# Voeding.net
KiCad netlist of a schematic drawn in Altium Designer
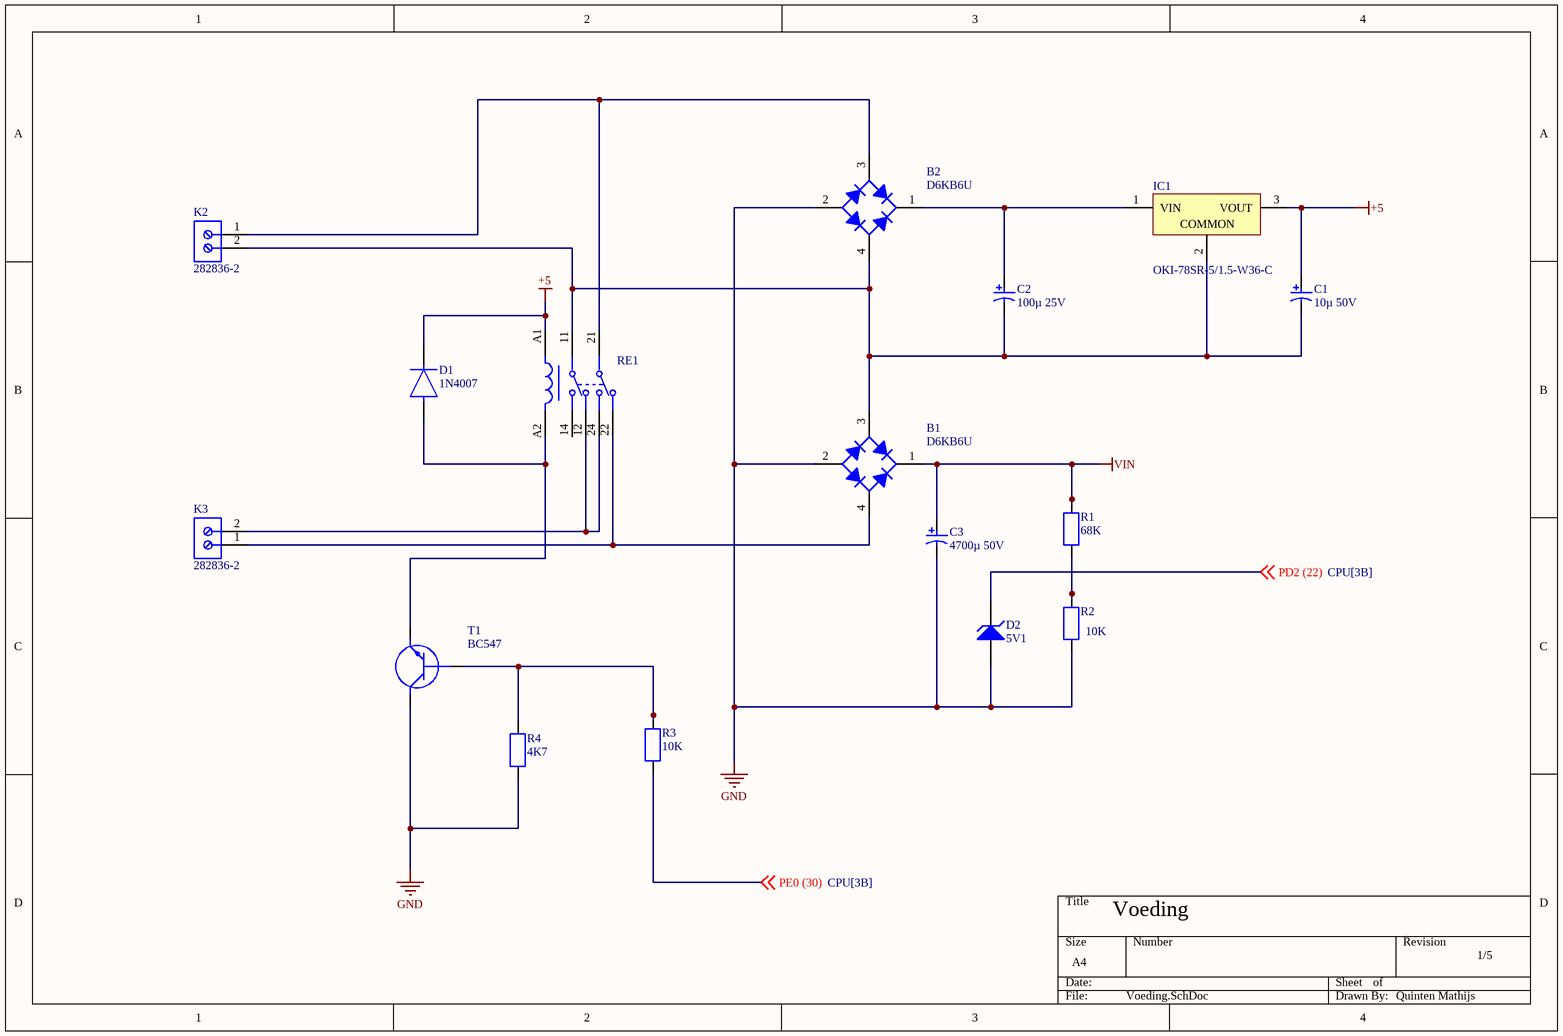
[diagram p0: Voeding.SchDoc]

(export (version "E")
  (design (tool "Eeschema 10.0.6"))
  (components
    (comp (ref "B1")
      (value "D6KB6U")
      (footprint "ttf")
      (fields (field (name "MANUFACTURER") "Diodes Inc"))
      (libsource (lib "Schem_Soldeerstation") (part "Bridge_Rectifier"))
    )
    (comp (ref "B2")
      (value "D6KB6U")
      (footprint "ttf")
      (fields (field (name "MANUFACTURER") "Diodes Inc"))
      (libsource (lib "Schem_Soldeerstation") (part "Bridge_Rectifier"))
    )
    (comp (ref "C1")
      (value "10µ 50V")
      (footprint "CE_D8_L10")
      (fields (field (name "MANUFACTURER") "Panasonic"))
      (libsource (lib "Schem_Soldeerstation") (part "Capacitor_Electrolytic"))
    )
    (comp (ref "C2")
      (value "100µ 25V")
      (footprint "CE_D8_L10")
      (fields (field (name "MANUFACTURER") "Panasonic"))
      (libsource (lib "Schem_Soldeerstation") (part "Capacitor_Electrolytic"))
    )
    (comp (ref "C3")
      (value "4700µ 50V")
      (footprint "CE_D25_L25_plugin")
      (fields (field (name "MANUFACTURER") "Panasonic"))
      (libsource (lib "Schem_Soldeerstation") (part "Capacitor_Electrolytic"))
    )
    (comp (ref "D1")
      (value "1N4007")
      (footprint "SOD-123FL")
      (fields
        (field (name "MANUFACTURER") "Diotec")
        (field (name "OCTOPART") "https://octopart.com/1n4007-diotec-4040411")
      )
      (libsource (lib "Schem_Soldeerstation") (part "Diode"))
    )
    (comp (ref "D2")
      (value "5V1")
      (footprint "SOD-123FL")
      (fields (field (name "MANUFACTURER") "On Semiconductor") (field (name "PARTNUMBER") "1SMB5920BT3G"))
      (libsource (lib "Schem_Soldeerstation") (part "Zener_Diode"))
    )
    (comp (ref "IC1")
      (value "OKI-78SR-5/1.5-W36-C")
      (footprint "OKI78SR515W36C")
      (description "Non-Isolated DC/DC Converter, 7.5 W, 7 to 36 V, 1.5 A, -40 to 85 degC, 3-Pin THD, RoHS")
      (fields (field (name "MANUFACTURER") "Murata"))
      (libsource (lib "Schem_Soldeerstation") (part "OKI-78SR-5/1.5-W36-C"))
    )
    (comp (ref "K2")
      (value "282836-2")
      (footprint "TECO-282836-2_V")
      (description "Female Header, Pitch 5 mm, 1 x 2 Position, Height 10 mm, Tail Length 3.5 mm, Rohs, Bulk")
      (fields (field (name "VOLTAGE") "300V") (field (name "MANUFACTURER") "TE Connectivity"))
      (libsource (lib "Schem_Soldeerstation") (part "CMP-1684-00017-1"))
    )
    (comp (ref "K3")
      (value "282836-2")
      (footprint "TECO-282836-2_V")
      (description "Female Header, Pitch 5 mm, 1 x 2 Position, Height 10 mm, Tail Length 3.5 mm, Rohs, Bulk")
      (fields (field (name "VOLTAGE") "300V") (field (name "MANUFACTURER") "TE Connectivity"))
      (libsource (lib "Schem_Soldeerstation") (part "CMP-1684-00017-1"))
    )
    (comp (ref "R1")
      (value "68K")
      (footprint "R_0805_L")
      (description "Resistor")
      (fields (field (name "MANUFACTURER") "Vishay Dale") (field (name "PART NUMBER") "CRCW08050000Z0EA"))
      (libsource (lib "Schem_Soldeerstation") (part "0805 (Resistor)"))
    )
    (comp (ref "R2")
      (value "10K")
      (footprint "R_0805_L")
      (description "Resistor")
      (fields (field (name "MANUFACTURER") "Vishay Dale") (field (name "PART NUMBER") "CRCW08050000Z0EA"))
      (libsource (lib "Schem_Soldeerstation") (part "0805 (Resistor)"))
    )
    (comp (ref "R3")
      (value "10K")
      (footprint "R_0805_L")
      (description "Resistor")
      (fields (field (name "MANUFACTURER") "Vishay Dale") (field (name "PART NUMBER") "CRCW08050000Z0EA"))
      (libsource (lib "Schem_Soldeerstation") (part "0805 (Resistor)"))
    )
    (comp (ref "R4")
      (value "4K7")
      (footprint "R_0805_L")
      (description "Resistor")
      (fields (field (name "MANUFACTURER") "Vishay Dale") (field (name "PART NUMBER") "CRCW08050000Z0EA"))
      (libsource (lib "Schem_Soldeerstation") (part "0805 (Resistor)"))
    )
    (comp (ref "RE1")
      (value "~")
      (footprint "RT42")
      (fields
        (field (name "MANUFACTURER PART NUMBER") "RT424005")
        (field (name "OCTOPART") "https://octopart.com/5-1393243-9-te+connectivity-41835766")
        (field (name "MANUFACTURER") "TE Connectivity")
      )
      (libsource (lib "Schem_Soldeerstation") (part "RELAY_GENERAL_PURPOSE"))
    )
    (comp (ref "T1")
      (value "BC547")
      (footprint "SOT_23")
      (fields (field (name "MANUFACTURER") "On Semiconductor") (field (name "PARTNUMBER") "BC547C"))
      (libsource (lib "Schem_Soldeerstation") (part "Transistor_NPN"))
    )
  )
  (nets
    (net (code "1") (name "+5") (class "Default")
      (node (ref "C1") (pin "2") (pinfunction "2_2") (pintype "passive"))
      (node (ref "D1") (pin "1") (pinfunction "C_1") (pintype "passive"))
      (node (ref "IC1") (pin "3") (pinfunction "VOUT_3") (pintype "power_in"))
      (node (ref "RE1") (pin "A1") (pinfunction "A1_A1") (pintype "passive"))
    )
    (net (code "2") (name "GND") (class "Default")
      (node (ref "B1") (pin "2") (pinfunction "A_2") (pintype "passive"))
      (node (ref "B2") (pin "2") (pinfunction "A_2") (pintype "passive"))
      (node (ref "C3") (pin "1") (pinfunction "1_1") (pintype "passive"))
      (node (ref "D2") (pin "2") (pinfunction "A_2") (pintype "passive"))
      (node (ref "R2") (pin "1") (pinfunction "1_1") (pintype "passive"))
      (node (ref "R4") (pin "1") (pinfunction "1_1") (pintype "passive"))
      (node (ref "T1") (pin "1") (pinfunction "C_1") (pintype "passive"))
    )
    (net (code "3") (name "Net-(B1-C-Pad4)") (class "Default")
      (node (ref "B1") (pin "4") (pinfunction "C_4") (pintype "passive"))
      (node (ref "K3") (pin "1") (pinfunction "1_1") (pintype "passive"))
      (node (ref "RE1") (pin "22") (pinfunction "22_22") (pintype "passive"))
    )
    (net (code "4") (name "Net-(B2-C-Pad3)") (class "Default")
      (node (ref "B2") (pin "3") (pinfunction "C_3") (pintype "passive"))
      (node (ref "K2") (pin "1") (pinfunction "1_1") (pintype "passive"))
      (node (ref "RE1") (pin "21") (pinfunction "21_21") (pintype "passive"))
    )
    (net (code "5") (name "Net-(B2-K)") (class "Default")
      (node (ref "B2") (pin "1") (pinfunction "K_1") (pintype "passive"))
      (node (ref "C2") (pin "2") (pinfunction "2_2") (pintype "passive"))
      (node (ref "IC1") (pin "1") (pinfunction "VIN_1") (pintype "power_in"))
    )
    (net (code "6") (name "Net-(D1-A)") (class "Default")
      (node (ref "D1") (pin "2") (pinfunction "A_2") (pintype "passive"))
      (node (ref "RE1") (pin "A2") (pinfunction "A2_A2") (pintype "passive"))
      (node (ref "T1") (pin "3") (pinfunction "E_3") (pintype "passive"))
    )
    (net (code "7") (name "Net-(IC1-COMMON)") (class "Default")
      (node (ref "B1") (pin "3") (pinfunction "C_3") (pintype "passive"))
      (node (ref "B2") (pin "4") (pinfunction "C_4") (pintype "passive"))
      (node (ref "C1") (pin "1") (pinfunction "1_1") (pintype "passive"))
      (node (ref "C2") (pin "1") (pinfunction "1_1") (pintype "passive"))
      (node (ref "IC1") (pin "2") (pinfunction "COMMON_2") (pintype "power_in"))
      (node (ref "K2") (pin "2") (pinfunction "2_2") (pintype "passive"))
      (node (ref "RE1") (pin "11") (pinfunction "11_11") (pintype "passive"))
    )
    (net (code "8") (name "Net-(K3-Pad2)") (class "Default")
      (node (ref "K3") (pin "2") (pinfunction "2_2") (pintype "passive"))
      (node (ref "RE1") (pin "12") (pinfunction "12_12") (pintype "passive"))
      (node (ref "RE1") (pin "24") (pinfunction "24_24") (pintype "passive"))
    )
    (net (code "9") (name "Net-(R1-Pad1)") (class "Default")
      (node (ref "R1") (pin "1") (pinfunction "1_1") (pintype "passive"))
      (node (ref "R2") (pin "2") (pinfunction "2_2") (pintype "passive"))
    )
    (net (code "10") (name "Net-(T1-B)") (class "Default")
      (node (ref "R3") (pin "2") (pinfunction "2_2") (pintype "passive"))
      (node (ref "R4") (pin "2") (pinfunction "2_2") (pintype "passive"))
      (node (ref "T1") (pin "2") (pinfunction "B_2") (pintype "passive"))
    )
    (net (code "11") (name "PD2 (22)") (class "Default")
      (node (ref "D2") (pin "1") (pinfunction "K_1") (pintype "passive"))
    )
    (net (code "12") (name "PE0 (30)") (class "Default")
      (node (ref "R3") (pin "1") (pinfunction "1_1") (pintype "passive"))
    )
    (net (code "13") (name "VIN") (class "Default")
      (node (ref "B1") (pin "1") (pinfunction "K_1") (pintype "passive"))
      (node (ref "C3") (pin "2") (pinfunction "2_2") (pintype "passive"))
      (node (ref "R1") (pin "2") (pinfunction "2_2") (pintype "passive"))
    )
    (net (code "14") (name "unconnected-(RE1-Pad14)") (class "Default")
      (node (ref "RE1") (pin "14") (pinfunction "14_14") (pintype "passive"))
    )
  )
)
